# schema5.net
KiCad netlist of a schematic drawn in Altium Designer
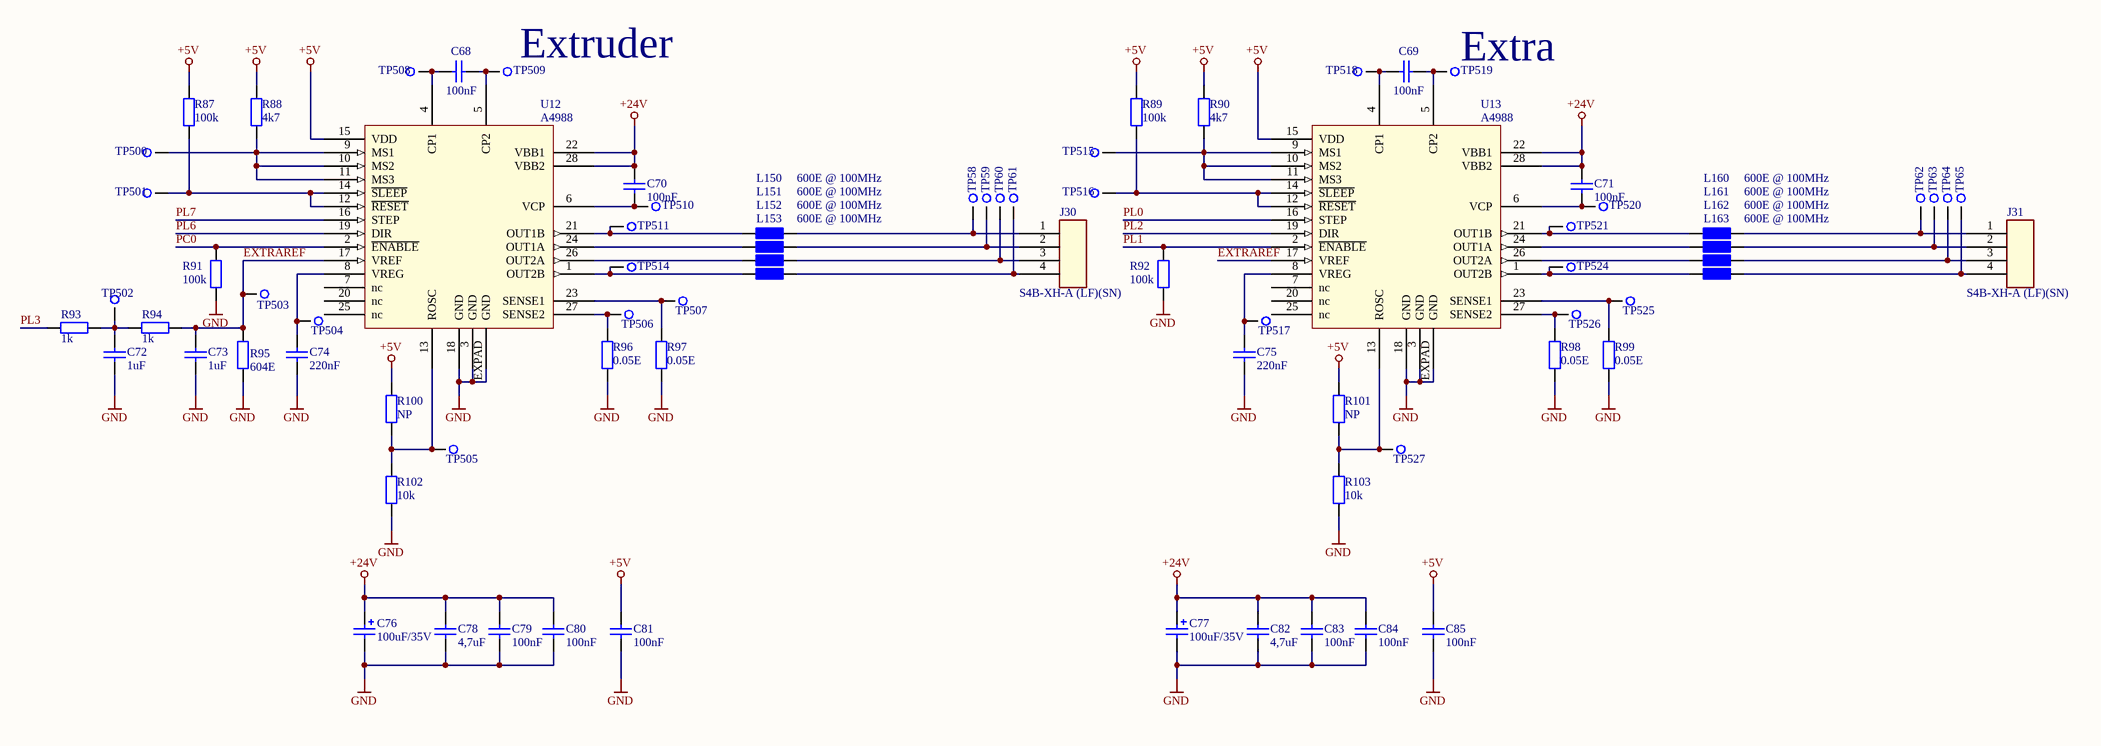
[diagram p0: schema5.SchDoc]

(export (version "E")
  (design (tool "Eeschema 10.0.6"))
  (components
    (comp (ref "C68")
      (value "100nF")
      (footprint "C0603")
      (description "RO X7R 100nF 10% 50V 0603")
      (libsource (lib "Database_Faber") (part "Capacitor"))
    )
    (comp (ref "C69")
      (value "100nF")
      (footprint "C0603")
      (description "RO X7R 100nF 10% 50V 0603")
      (libsource (lib "Database_Faber") (part "Capacitor"))
    )
    (comp (ref "C70")
      (value "100nF")
      (footprint "C0603")
      (description "RO X7R 100nF 10% 50V 0603")
      (libsource (lib "Database_Faber") (part "Capacitor"))
    )
    (comp (ref "C71")
      (value "100nF")
      (footprint "C0603")
      (description "RO X7R 100nF 10% 50V 0603")
      (libsource (lib "Database_Faber") (part "Capacitor"))
    )
    (comp (ref "C72")
      (value "1uF")
      (footprint "C0603")
      (description "RO X5R 1uF 10% 10V 0603")
      (libsource (lib "Database_Faber") (part "Capacitor"))
    )
    (comp (ref "C73")
      (value "1uF")
      (footprint "C0603")
      (description "RO X5R 1uF 10% 10V 0603")
      (libsource (lib "Database_Faber") (part "Capacitor"))
    )
    (comp (ref "C74")
      (value "220nF")
      (footprint "C0603")
      (description "RO X7R 220nF 10% 25V  0603")
      (libsource (lib "Database_Faber") (part "Capacitor"))
    )
    (comp (ref "C75")
      (value "220nF")
      (footprint "C0603")
      (description "RO X7R 220nF 10% 25V  0603")
      (libsource (lib "Database_Faber") (part "Capacitor"))
    )
    (comp (ref "C76")
      (value "100uF/35V")
      (footprint "ELCO Case D")
      (description "RO ELCO 100uF 20% 35V CASE-D EEEFP PAN")
      (libsource (lib "Database_Faber") (part "Capacitor Polarity"))
    )
    (comp (ref "C77")
      (value "100uF/35V")
      (footprint "ELCO Case D")
      (description "RO ELCO 100uF 20% 35V CASE-D EEEFP PAN")
      (libsource (lib "Database_Faber") (part "Capacitor Polarity"))
    )
    (comp (ref "C78")
      (value "4,7uF")
      (footprint "C1206")
      (description "RO X7R 4,7uF 10% 50V 1206")
      (libsource (lib "Database_Faber") (part "Capacitor"))
    )
    (comp (ref "C79")
      (value "100nF")
      (footprint "C0603")
      (description "RO X7R 100nF 10% 50V 0603")
      (libsource (lib "Database_Faber") (part "Capacitor"))
    )
    (comp (ref "C80")
      (value "100nF")
      (footprint "C0603")
      (description "RO X7R 100nF 10% 50V 0603")
      (libsource (lib "Database_Faber") (part "Capacitor"))
    )
    (comp (ref "C81")
      (value "100nF")
      (footprint "C0603")
      (description "RO X7R 100nF 10% 50V 0603")
      (libsource (lib "Database_Faber") (part "Capacitor"))
    )
    (comp (ref "C82")
      (value "4,7uF")
      (footprint "C1206")
      (description "RO X7R 4,7uF 10% 50V 1206")
      (libsource (lib "Database_Faber") (part "Capacitor"))
    )
    (comp (ref "C83")
      (value "100nF")
      (footprint "C0603")
      (description "RO X7R 100nF 10% 50V 0603")
      (libsource (lib "Database_Faber") (part "Capacitor"))
    )
    (comp (ref "C84")
      (value "100nF")
      (footprint "C0603")
      (description "RO X7R 100nF 10% 50V 0603")
      (libsource (lib "Database_Faber") (part "Capacitor"))
    )
    (comp (ref "C85")
      (value "100nF")
      (footprint "C0603")
      (description "RO X7R 100nF 10% 50V 0603")
      (libsource (lib "Database_Faber") (part "Capacitor"))
    )
    (comp (ref "J30")
      (value "S4B-XH-A (LF)(SN)")
      (footprint "S4B-XH-A (LF)(SN)")
      (description "RO CONN PR 4p HKS S4B-XH-A (LF)(SN) JST")
      (fields (field (name "MFG") "JST (JAPAN SOLDERLESS TERMINALS)"))
      (libsource (lib "Database_Faber") (part "HEADER 4"))
    )
    (comp (ref "J31")
      (value "S4B-XH-A (LF)(SN)")
      (footprint "S4B-XH-A (LF)(SN)")
      (description "RO CONN PR 4p HKS S4B-XH-A (LF)(SN) JST")
      (fields (field (name "MFG") "JST (JAPAN SOLDERLESS TERMINALS)"))
      (libsource (lib "Database_Faber") (part "HEADER 4"))
    )
    (comp (ref "L150")
      (value "600E @ 100MHz")
      (footprint "R1206")
      (description "FERRIET 742792118 1206 Wurth Elektronik")
      (fields (field (name "MFG") "Wurth Elektronics"))
      (libsource (lib "Ultimaker") (part "Ferriet Bead 600E"))
    )
    (comp (ref "L151")
      (value "600E @ 100MHz")
      (footprint "R1206")
      (description "FERRIET 742792118 1206 Wurth Elektronik")
      (fields (field (name "MFG") "Wurth Elektronics"))
      (libsource (lib "Ultimaker") (part "Ferriet Bead 600E"))
    )
    (comp (ref "L152")
      (value "600E @ 100MHz")
      (footprint "R1206")
      (description "FERRIET 742792118 1206 Wurth Elektronik")
      (fields (field (name "MFG") "Wurth Elektronics"))
      (libsource (lib "Ultimaker") (part "Ferriet Bead 600E"))
    )
    (comp (ref "L153")
      (value "600E @ 100MHz")
      (footprint "R1206")
      (description "FERRIET 742792118 1206 Wurth Elektronik")
      (fields (field (name "MFG") "Wurth Elektronics"))
      (libsource (lib "Ultimaker") (part "Ferriet Bead 600E"))
    )
    (comp (ref "L160")
      (value "600E @ 100MHz")
      (footprint "R1206")
      (description "FERRIET 742792118 1206 Wurth Elektronik")
      (fields (field (name "MFG") "Wurth Elektronics"))
      (libsource (lib "Ultimaker") (part "Ferriet Bead 600E"))
    )
    (comp (ref "L161")
      (value "600E @ 100MHz")
      (footprint "R1206")
      (description "FERRIET 742792118 1206 Wurth Elektronik")
      (fields (field (name "MFG") "Wurth Elektronics"))
      (libsource (lib "Ultimaker") (part "Ferriet Bead 600E"))
    )
    (comp (ref "L162")
      (value "600E @ 100MHz")
      (footprint "R1206")
      (description "FERRIET 742792118 1206 Wurth Elektronik")
      (fields (field (name "MFG") "Wurth Elektronics"))
      (libsource (lib "Ultimaker") (part "Ferriet Bead 600E"))
    )
    (comp (ref "L163")
      (value "600E @ 100MHz")
      (footprint "R1206")
      (description "FERRIET 742792118 1206 Wurth Elektronik")
      (fields (field (name "MFG") "Wurth Elektronics"))
      (libsource (lib "Ultimaker") (part "Ferriet Bead 600E"))
    )
    (comp (ref "R87")
      (value "100k")
      (footprint "R0603")
      (description "RO RES 100k0 1% 0,063W  0603")
      (libsource (lib "") (part "Resistor_1"))
    )
    (comp (ref "R88")
      (value "4k7")
      (footprint "R0603")
      (description "RO RES 4k70 1% 0,063W  0603")
      (libsource (lib "") (part "Resistor_1"))
    )
    (comp (ref "R89")
      (value "100k")
      (footprint "R0603")
      (description "RO RES 100k0 1% 0,063W  0603")
      (libsource (lib "") (part "Resistor_1"))
    )
    (comp (ref "R90")
      (value "4k7")
      (footprint "R0603")
      (description "RO RES 4k70 1% 0,063W  0603")
      (libsource (lib "") (part "Resistor_1"))
    )
    (comp (ref "R91")
      (value "100k")
      (footprint "R0603")
      (description "RO RES 100k0 1% 0,063W  0603")
      (libsource (lib "Database_Faber") (part "Resistor"))
    )
    (comp (ref "R92")
      (value "100k")
      (footprint "R0603")
      (description "RO RES 100k0 1% 0,063W  0603")
      (libsource (lib "Database_Faber") (part "Resistor"))
    )
    (comp (ref "R93")
      (value "1k")
      (footprint "R0603")
      (description "RO RES 1k0 1% 0,1W  0603")
      (libsource (lib "") (part "Resistor_2"))
    )
    (comp (ref "R94")
      (value "1k")
      (footprint "R0603")
      (description "RO RES 1k0 1% 0,1W  0603")
      (libsource (lib "") (part "Resistor_2"))
    )
    (comp (ref "R95")
      (value "604E")
      (footprint "R0603")
      (description "RO RES 604E 1% 0,063W 0603")
      (fields (field (name "MFG") "VISHAY DRALORIC"))
      (libsource (lib "") (part "Resistor_1"))
    )
    (comp (ref "R96")
      (value "0.05E")
      (footprint "R0805")
      (description "RO RES 0E05 1% 0,125W 0805")
      (fields (field (name "MFG") "BOURNS"))
      (libsource (lib "") (part "Resistor_1"))
    )
    (comp (ref "R97")
      (value "0.05E")
      (footprint "R0805")
      (description "RO RES 0E05 1% 0,125W 0805")
      (fields (field (name "MFG") "BOURNS"))
      (libsource (lib "") (part "Resistor_1"))
    )
    (comp (ref "R98")
      (value "0.05E")
      (footprint "R0805")
      (description "RO RES 0E05 1% 0,125W 0805")
      (fields (field (name "MFG") "BOURNS"))
      (libsource (lib "") (part "Resistor_1"))
    )
    (comp (ref "R99")
      (value "0.05E")
      (footprint "R0805")
      (description "RO RES 0E05 1% 0,125W 0805")
      (fields (field (name "MFG") "BOURNS"))
      (libsource (lib "") (part "Resistor_1"))
    )
    (comp (ref "R100") (value "NP") (footprint "R0603") (libsource (lib "") (part "Resistor_1")))
    (comp (ref "R101") (value "NP") (footprint "R0603") (libsource (lib "") (part "Resistor_1")))
    (comp (ref "R102")
      (value "10k")
      (footprint "R0603")
      (description "RO RES 10k0 1% 0,063W  0603")
      (libsource (lib "") (part "Resistor_1"))
    )
    (comp (ref "R103")
      (value "10k")
      (footprint "R0603")
      (description "RO RES 10k0 1% 0,063W  0603")
      (libsource (lib "") (part "Resistor_1"))
    )
    (comp (ref "TP58")
      (value "Testpoint")
      (footprint "Testpoint")
      (libsource (lib "Database_Faber") (part "Testpoint"))
    )
    (comp (ref "TP59")
      (value "Testpoint")
      (footprint "Testpoint")
      (libsource (lib "Database_Faber") (part "Testpoint"))
    )
    (comp (ref "TP60")
      (value "Testpoint")
      (footprint "Testpoint")
      (libsource (lib "Database_Faber") (part "Testpoint"))
    )
    (comp (ref "TP61")
      (value "Testpoint")
      (footprint "Testpoint")
      (libsource (lib "Database_Faber") (part "Testpoint"))
    )
    (comp (ref "TP62")
      (value "Testpoint")
      (footprint "Testpoint")
      (libsource (lib "Database_Faber") (part "Testpoint"))
    )
    (comp (ref "TP63")
      (value "Testpoint")
      (footprint "Testpoint")
      (libsource (lib "Database_Faber") (part "Testpoint"))
    )
    (comp (ref "TP64")
      (value "Testpoint")
      (footprint "Testpoint")
      (libsource (lib "Database_Faber") (part "Testpoint"))
    )
    (comp (ref "TP65")
      (value "Testpoint")
      (footprint "Testpoint")
      (libsource (lib "Database_Faber") (part "Testpoint"))
    )
    (comp (ref "TP500")
      (value "Testpoint 1mm")
      (footprint "Testpoint 1mm")
      (libsource (lib "Ultimaker") (part "Testpoint 1mm"))
    )
    (comp (ref "TP501")
      (value "Testpoint 1mm")
      (footprint "Testpoint 1mm")
      (libsource (lib "Ultimaker") (part "Testpoint 1mm"))
    )
    (comp (ref "TP502")
      (value "Testpoint 1mm")
      (footprint "Testpoint 1mm")
      (libsource (lib "Ultimaker") (part "Testpoint 1mm"))
    )
    (comp (ref "TP503")
      (value "Testpoint 1mm")
      (footprint "Testpoint 1mm")
      (libsource (lib "Ultimaker") (part "Testpoint 1mm"))
    )
    (comp (ref "TP504")
      (value "Testpoint 1mm")
      (footprint "Testpoint 1mm")
      (libsource (lib "Ultimaker") (part "Testpoint 1mm"))
    )
    (comp (ref "TP505")
      (value "Testpoint 1mm")
      (footprint "Testpoint 1mm")
      (libsource (lib "Ultimaker") (part "Testpoint 1mm"))
    )
    (comp (ref "TP506")
      (value "Testpoint 1mm")
      (footprint "Testpoint 1mm")
      (libsource (lib "Ultimaker") (part "Testpoint 1mm"))
    )
    (comp (ref "TP507")
      (value "Testpoint 1mm")
      (footprint "Testpoint 1mm")
      (libsource (lib "Ultimaker") (part "Testpoint 1mm"))
    )
    (comp (ref "TP508")
      (value "Testpoint 1mm")
      (footprint "Testpoint 1mm")
      (libsource (lib "Ultimaker") (part "Testpoint 1mm"))
    )
    (comp (ref "TP509")
      (value "Testpoint 1mm")
      (footprint "Testpoint 1mm")
      (libsource (lib "Ultimaker") (part "Testpoint 1mm"))
    )
    (comp (ref "TP510")
      (value "Testpoint 1mm")
      (footprint "Testpoint 1mm")
      (libsource (lib "Ultimaker") (part "Testpoint 1mm"))
    )
    (comp (ref "TP511")
      (value "Testpoint 1mm")
      (footprint "Testpoint 1mm")
      (libsource (lib "Ultimaker") (part "Testpoint 1mm"))
    )
    (comp (ref "TP514")
      (value "Testpoint 1mm")
      (footprint "Testpoint 1mm")
      (libsource (lib "Ultimaker") (part "Testpoint 1mm"))
    )
    (comp (ref "TP515")
      (value "Testpoint 1mm")
      (footprint "Testpoint 1mm")
      (libsource (lib "Ultimaker") (part "Testpoint 1mm"))
    )
    (comp (ref "TP516")
      (value "Testpoint 1mm")
      (footprint "Testpoint 1mm")
      (libsource (lib "Ultimaker") (part "Testpoint 1mm"))
    )
    (comp (ref "TP517")
      (value "Testpoint 1mm")
      (footprint "Testpoint 1mm")
      (libsource (lib "Ultimaker") (part "Testpoint 1mm"))
    )
    (comp (ref "TP518")
      (value "Testpoint 1mm")
      (footprint "Testpoint 1mm")
      (libsource (lib "Ultimaker") (part "Testpoint 1mm"))
    )
    (comp (ref "TP519")
      (value "Testpoint 1mm")
      (footprint "Testpoint 1mm")
      (libsource (lib "Ultimaker") (part "Testpoint 1mm"))
    )
    (comp (ref "TP520")
      (value "Testpoint 1mm")
      (footprint "Testpoint 1mm")
      (libsource (lib "Ultimaker") (part "Testpoint 1mm"))
    )
    (comp (ref "TP521")
      (value "Testpoint 1mm")
      (footprint "Testpoint 1mm")
      (libsource (lib "Ultimaker") (part "Testpoint 1mm"))
    )
    (comp (ref "TP524")
      (value "Testpoint 1mm")
      (footprint "Testpoint 1mm")
      (libsource (lib "Ultimaker") (part "Testpoint 1mm"))
    )
    (comp (ref "TP525")
      (value "Testpoint 1mm")
      (footprint "Testpoint 1mm")
      (libsource (lib "Ultimaker") (part "Testpoint 1mm"))
    )
    (comp (ref "TP526")
      (value "Testpoint 1mm")
      (footprint "Testpoint 1mm")
      (libsource (lib "Ultimaker") (part "Testpoint 1mm"))
    )
    (comp (ref "TP527")
      (value "Testpoint 1mm")
      (footprint "Testpoint 1mm")
      (libsource (lib "Ultimaker") (part "Testpoint 1mm"))
    )
    (comp (ref "U12")
      (value "A4988")
      (footprint "QFN50P500X500X100-28-EX")
      (description "RO IC A4988 QFN-28 ALLEGRO")
      (fields (field (name "MFG") "Allegro"))
      (libsource (lib "Database_Faber") (part "A4988"))
    )
    (comp (ref "U13")
      (value "A4988")
      (footprint "QFN50P500X500X100-28-EX")
      (description "RO IC A4988 QFN-28 ALLEGRO")
      (fields (field (name "MFG") "Allegro"))
      (libsource (lib "Database_Faber") (part "A4988"))
    )
  )
  (nets
    (net (code "1") (name "+5V") (class "Default")
      (node (ref "C81") (pin "2") (pinfunction "2_2") (pintype "passive"))
      (node (ref "C85") (pin "2") (pinfunction "2_2") (pintype "passive"))
      (node (ref "R100") (pin "2") (pinfunction "2_2") (pintype "passive"))
      (node (ref "R101") (pin "2") (pinfunction "2_2") (pintype "passive"))
      (node (ref "R87") (pin "2") (pinfunction "2_2") (pintype "passive"))
      (node (ref "R88") (pin "2") (pinfunction "2_2") (pintype "passive"))
      (node (ref "R89") (pin "2") (pinfunction "2_2") (pintype "passive"))
      (node (ref "R90") (pin "2") (pinfunction "2_2") (pintype "passive"))
      (node (ref "U12") (pin "15") (pinfunction "VDD_15") (pintype "power_in"))
      (node (ref "U13") (pin "15") (pinfunction "VDD_15") (pintype "power_in"))
    )
    (net (code "2") (name "+24V") (class "Default")
      (node (ref "C70") (pin "2") (pinfunction "2_2") (pintype "passive"))
      (node (ref "C71") (pin "2") (pinfunction "2_2") (pintype "passive"))
      (node (ref "C76") (pin "1") (pinfunction "1_1") (pintype "passive"))
      (node (ref "C77") (pin "1") (pinfunction "1_1") (pintype "passive"))
      (node (ref "C78") (pin "2") (pinfunction "2_2") (pintype "passive"))
      (node (ref "C79") (pin "2") (pinfunction "2_2") (pintype "passive"))
      (node (ref "C80") (pin "2") (pinfunction "2_2") (pintype "passive"))
      (node (ref "C82") (pin "2") (pinfunction "2_2") (pintype "passive"))
      (node (ref "C83") (pin "2") (pinfunction "2_2") (pintype "passive"))
      (node (ref "C84") (pin "2") (pinfunction "2_2") (pintype "passive"))
      (node (ref "U12") (pin "22") (pinfunction "VBB1_22") (pintype "power_in"))
      (node (ref "U12") (pin "28") (pinfunction "VBB2_28") (pintype "power_in"))
      (node (ref "U13") (pin "22") (pinfunction "VBB1_22") (pintype "power_in"))
      (node (ref "U13") (pin "28") (pinfunction "VBB2_28") (pintype "power_in"))
    )
    (net (code "3") (name "/EXTRAREF") (class "Default")
      (node (ref "C73") (pin "2") (pinfunction "2_2") (pintype "passive"))
      (node (ref "R94") (pin "2") (pinfunction "2_2") (pintype "passive"))
      (node (ref "R95") (pin "2") (pinfunction "2_2") (pintype "passive"))
      (node (ref "TP503") (pin "1") (pinfunction "1_1") (pintype "passive"))
      (node (ref "U12") (pin "17") (pinfunction "VREF_17") (pintype "input"))
      (node (ref "U13") (pin "17") (pinfunction "VREF_17") (pintype "input"))
    )
    (net (code "4") (name "/PC0") (class "Default")
      (node (ref "R91") (pin "1") (pinfunction "1_1") (pintype "passive"))
      (node (ref "U12") (pin "2") (pinfunction "~{ENABLE}_2") (pintype "input"))
    )
    (net (code "5") (name "/PL0") (class "Default")
      (node (ref "U13") (pin "16") (pinfunction "STEP_16") (pintype "input"))
    )
    (net (code "6") (name "/PL1") (class "Default")
      (node (ref "R92") (pin "1") (pinfunction "1_1") (pintype "passive"))
      (node (ref "U13") (pin "2") (pinfunction "~{ENABLE}_2") (pintype "input"))
    )
    (net (code "7") (name "/PL2") (class "Default")
      (node (ref "U13") (pin "19") (pinfunction "DIR_19") (pintype "input"))
    )
    (net (code "8") (name "/PL3") (class "Default")
      (node (ref "R93") (pin "1") (pinfunction "1_1") (pintype "passive"))
    )
    (net (code "9") (name "/PL6") (class "Default")
      (node (ref "U12") (pin "19") (pinfunction "DIR_19") (pintype "input"))
    )
    (net (code "10") (name "/PL7") (class "Default")
      (node (ref "U12") (pin "16") (pinfunction "STEP_16") (pintype "input"))
    )
    (net (code "11") (name "GND") (class "Default")
      (node (ref "C72") (pin "1") (pinfunction "1_1") (pintype "passive"))
      (node (ref "C73") (pin "1") (pinfunction "1_1") (pintype "passive"))
      (node (ref "C74") (pin "1") (pinfunction "1_1") (pintype "passive"))
      (node (ref "C75") (pin "1") (pinfunction "1_1") (pintype "passive"))
      (node (ref "C76") (pin "2") (pinfunction "2_2") (pintype "passive"))
      (node (ref "C77") (pin "2") (pinfunction "2_2") (pintype "passive"))
      (node (ref "C78") (pin "1") (pinfunction "1_1") (pintype "passive"))
      (node (ref "C79") (pin "1") (pinfunction "1_1") (pintype "passive"))
      (node (ref "C80") (pin "1") (pinfunction "1_1") (pintype "passive"))
      (node (ref "C81") (pin "1") (pinfunction "1_1") (pintype "passive"))
      (node (ref "C82") (pin "1") (pinfunction "1_1") (pintype "passive"))
      (node (ref "C83") (pin "1") (pinfunction "1_1") (pintype "passive"))
      (node (ref "C84") (pin "1") (pinfunction "1_1") (pintype "passive"))
      (node (ref "C85") (pin "1") (pinfunction "1_1") (pintype "passive"))
      (node (ref "R102") (pin "1") (pinfunction "1_1") (pintype "passive"))
      (node (ref "R103") (pin "1") (pinfunction "1_1") (pintype "passive"))
      (node (ref "R91") (pin "2") (pinfunction "2_2") (pintype "passive"))
      (node (ref "R92") (pin "2") (pinfunction "2_2") (pintype "passive"))
      (node (ref "R95") (pin "1") (pinfunction "1_1") (pintype "passive"))
      (node (ref "R96") (pin "1") (pinfunction "1_1") (pintype "passive"))
      (node (ref "R97") (pin "1") (pinfunction "1_1") (pintype "passive"))
      (node (ref "R98") (pin "1") (pinfunction "1_1") (pintype "passive"))
      (node (ref "R99") (pin "1") (pinfunction "1_1") (pintype "passive"))
      (node (ref "U12") (pin "18") (pinfunction "GND_18") (pintype "passive"))
      (node (ref "U12") (pin "3") (pinfunction "GND_3") (pintype "power_in"))
      (node (ref "U12") (pin "EXPAD") (pinfunction "GND_EXPAD") (pintype "power_in"))
      (node (ref "U13") (pin "18") (pinfunction "GND_18") (pintype "passive"))
      (node (ref "U13") (pin "3") (pinfunction "GND_3") (pintype "power_in"))
      (node (ref "U13") (pin "EXPAD") (pinfunction "GND_EXPAD") (pintype "power_in"))
    )
    (net (code "12") (name "Net-(C72-Pad2)") (class "Default")
      (node (ref "C72") (pin "2") (pinfunction "2_2") (pintype "passive"))
      (node (ref "R93") (pin "2") (pinfunction "2_2") (pintype "passive"))
      (node (ref "R94") (pin "1") (pinfunction "1_1") (pintype "passive"))
      (node (ref "TP502") (pin "1") (pinfunction "1_1") (pintype "passive"))
    )
    (net (code "13") (name "Net-(J30-Pad1)") (class "Default")
      (node (ref "J30") (pin "1") (pinfunction "1_1") (pintype "passive"))
      (node (ref "L150") (pin "2") (pinfunction "2_2") (pintype "passive"))
      (node (ref "TP58") (pin "1") (pinfunction "1_1") (pintype "passive"))
    )
    (net (code "14") (name "Net-(J30-Pad2)") (class "Default")
      (node (ref "J30") (pin "2") (pinfunction "2_2") (pintype "passive"))
      (node (ref "L151") (pin "2") (pinfunction "2_2") (pintype "passive"))
      (node (ref "TP59") (pin "1") (pinfunction "1_1") (pintype "passive"))
    )
    (net (code "15") (name "Net-(J30-Pad3)") (class "Default")
      (node (ref "J30") (pin "3") (pinfunction "3_3") (pintype "passive"))
      (node (ref "L152") (pin "2") (pinfunction "2_2") (pintype "passive"))
      (node (ref "TP60") (pin "1") (pinfunction "1_1") (pintype "passive"))
    )
    (net (code "16") (name "Net-(J30-Pad4)") (class "Default")
      (node (ref "J30") (pin "4") (pinfunction "4_4") (pintype "passive"))
      (node (ref "L153") (pin "2") (pinfunction "2_2") (pintype "passive"))
      (node (ref "TP61") (pin "1") (pinfunction "1_1") (pintype "passive"))
    )
    (net (code "17") (name "Net-(J31-Pad1)") (class "Default")
      (node (ref "J31") (pin "1") (pinfunction "1_1") (pintype "passive"))
      (node (ref "L160") (pin "2") (pinfunction "2_2") (pintype "passive"))
      (node (ref "TP62") (pin "1") (pinfunction "1_1") (pintype "passive"))
    )
    (net (code "18") (name "Net-(J31-Pad2)") (class "Default")
      (node (ref "J31") (pin "2") (pinfunction "2_2") (pintype "passive"))
      (node (ref "L161") (pin "2") (pinfunction "2_2") (pintype "passive"))
      (node (ref "TP63") (pin "1") (pinfunction "1_1") (pintype "passive"))
    )
    (net (code "19") (name "Net-(J31-Pad3)") (class "Default")
      (node (ref "J31") (pin "3") (pinfunction "3_3") (pintype "passive"))
      (node (ref "L162") (pin "2") (pinfunction "2_2") (pintype "passive"))
      (node (ref "TP64") (pin "1") (pinfunction "1_1") (pintype "passive"))
    )
    (net (code "20") (name "Net-(J31-Pad4)") (class "Default")
      (node (ref "J31") (pin "4") (pinfunction "4_4") (pintype "passive"))
      (node (ref "L163") (pin "2") (pinfunction "2_2") (pintype "passive"))
      (node (ref "TP65") (pin "1") (pinfunction "1_1") (pintype "passive"))
    )
    (net (code "21") (name "Net-(U12-CP1)") (class "Default")
      (node (ref "C68") (pin "1") (pinfunction "1_1") (pintype "passive"))
      (node (ref "TP508") (pin "1") (pinfunction "1_1") (pintype "passive"))
      (node (ref "U12") (pin "4") (pinfunction "CP1_4") (pintype "passive"))
    )
    (net (code "22") (name "Net-(U12-CP2)") (class "Default")
      (node (ref "C68") (pin "2") (pinfunction "2_2") (pintype "passive"))
      (node (ref "TP509") (pin "1") (pinfunction "1_1") (pintype "passive"))
      (node (ref "U12") (pin "5") (pinfunction "CP2_5") (pintype "passive"))
    )
    (net (code "23") (name "Net-(U12-MS1)") (class "Default")
      (node (ref "R88") (pin "1") (pinfunction "1_1") (pintype "passive"))
      (node (ref "TP500") (pin "1") (pinfunction "1_1") (pintype "passive"))
      (node (ref "U12") (pin "10") (pinfunction "MS2_10") (pintype "input"))
      (node (ref "U12") (pin "11") (pinfunction "MS3_11") (pintype "input"))
      (node (ref "U12") (pin "9") (pinfunction "MS1_9") (pintype "input"))
    )
    (net (code "24") (name "Net-(U12-OUT1A)") (class "Default")
      (node (ref "L151") (pin "1") (pinfunction "1_1") (pintype "passive"))
      (node (ref "U12") (pin "24") (pinfunction "OUT1A_24") (pintype "output"))
    )
    (net (code "25") (name "Net-(U12-OUT1B)") (class "Default")
      (node (ref "L150") (pin "1") (pinfunction "1_1") (pintype "passive"))
      (node (ref "TP511") (pin "1") (pinfunction "1_1") (pintype "passive"))
      (node (ref "U12") (pin "21") (pinfunction "OUT1B_21") (pintype "output"))
    )
    (net (code "26") (name "Net-(U12-OUT2A)") (class "Default")
      (node (ref "L152") (pin "1") (pinfunction "1_1") (pintype "passive"))
      (node (ref "U12") (pin "26") (pinfunction "OUT2A_26") (pintype "output"))
    )
    (net (code "27") (name "Net-(U12-OUT2B)") (class "Default")
      (node (ref "L153") (pin "1") (pinfunction "1_1") (pintype "passive"))
      (node (ref "TP514") (pin "1") (pinfunction "1_1") (pintype "passive"))
      (node (ref "U12") (pin "1") (pinfunction "OUT2B_1") (pintype "output"))
    )
    (net (code "28") (name "Net-(U12-ROSC)") (class "Default")
      (node (ref "R100") (pin "1") (pinfunction "1_1") (pintype "passive"))
      (node (ref "R102") (pin "2") (pinfunction "2_2") (pintype "passive"))
      (node (ref "TP505") (pin "1") (pinfunction "1_1") (pintype "passive"))
      (node (ref "U12") (pin "13") (pinfunction "ROSC_13") (pintype "passive"))
    )
    (net (code "29") (name "Net-(U12-SENSE1)") (class "Default")
      (node (ref "R97") (pin "2") (pinfunction "2_2") (pintype "passive"))
      (node (ref "TP507") (pin "1") (pinfunction "1_1") (pintype "passive"))
      (node (ref "U12") (pin "23") (pinfunction "SENSE1_23") (pintype "passive"))
    )
    (net (code "30") (name "Net-(U12-SENSE2)") (class "Default")
      (node (ref "R96") (pin "2") (pinfunction "2_2") (pintype "passive"))
      (node (ref "TP506") (pin "1") (pinfunction "1_1") (pintype "passive"))
      (node (ref "U12") (pin "27") (pinfunction "SENSE2_27") (pintype "passive"))
    )
    (net (code "31") (name "Net-(U12-VCP)") (class "Default")
      (node (ref "C70") (pin "1") (pinfunction "1_1") (pintype "passive"))
      (node (ref "TP510") (pin "1") (pinfunction "1_1") (pintype "passive"))
      (node (ref "U12") (pin "6") (pinfunction "VCP_6") (pintype "passive"))
    )
    (net (code "32") (name "Net-(U12-VREG)") (class "Default")
      (node (ref "C74") (pin "2") (pinfunction "2_2") (pintype "passive"))
      (node (ref "TP504") (pin "1") (pinfunction "1_1") (pintype "passive"))
      (node (ref "U12") (pin "8") (pinfunction "VREG_8") (pintype "power_in"))
    )
    (net (code "33") (name "Net-(U12-~{RESET})") (class "Default")
      (node (ref "R87") (pin "1") (pinfunction "1_1") (pintype "passive"))
      (node (ref "TP501") (pin "1") (pinfunction "1_1") (pintype "passive"))
      (node (ref "U12") (pin "12") (pinfunction "~{RESET}_12") (pintype "input"))
      (node (ref "U12") (pin "14") (pinfunction "~{SLEEP}_14") (pintype "input"))
    )
    (net (code "34") (name "Net-(U13-CP1)") (class "Default")
      (node (ref "C69") (pin "1") (pinfunction "1_1") (pintype "passive"))
      (node (ref "TP518") (pin "1") (pinfunction "1_1") (pintype "passive"))
      (node (ref "U13") (pin "4") (pinfunction "CP1_4") (pintype "passive"))
    )
    (net (code "35") (name "Net-(U13-CP2)") (class "Default")
      (node (ref "C69") (pin "2") (pinfunction "2_2") (pintype "passive"))
      (node (ref "TP519") (pin "1") (pinfunction "1_1") (pintype "passive"))
      (node (ref "U13") (pin "5") (pinfunction "CP2_5") (pintype "passive"))
    )
    (net (code "36") (name "Net-(U13-MS1)") (class "Default")
      (node (ref "R90") (pin "1") (pinfunction "1_1") (pintype "passive"))
      (node (ref "TP515") (pin "1") (pinfunction "1_1") (pintype "passive"))
      (node (ref "U13") (pin "10") (pinfunction "MS2_10") (pintype "input"))
      (node (ref "U13") (pin "11") (pinfunction "MS3_11") (pintype "input"))
      (node (ref "U13") (pin "9") (pinfunction "MS1_9") (pintype "input"))
    )
    (net (code "37") (name "Net-(U13-OUT1A)") (class "Default")
      (node (ref "L161") (pin "1") (pinfunction "1_1") (pintype "passive"))
      (node (ref "U13") (pin "24") (pinfunction "OUT1A_24") (pintype "output"))
    )
    (net (code "38") (name "Net-(U13-OUT1B)") (class "Default")
      (node (ref "L160") (pin "1") (pinfunction "1_1") (pintype "passive"))
      (node (ref "TP521") (pin "1") (pinfunction "1_1") (pintype "passive"))
      (node (ref "U13") (pin "21") (pinfunction "OUT1B_21") (pintype "output"))
    )
    (net (code "39") (name "Net-(U13-OUT2A)") (class "Default")
      (node (ref "L162") (pin "1") (pinfunction "1_1") (pintype "passive"))
      (node (ref "U13") (pin "26") (pinfunction "OUT2A_26") (pintype "output"))
    )
    (net (code "40") (name "Net-(U13-OUT2B)") (class "Default")
      (node (ref "L163") (pin "1") (pinfunction "1_1") (pintype "passive"))
      (node (ref "TP524") (pin "1") (pinfunction "1_1") (pintype "passive"))
      (node (ref "U13") (pin "1") (pinfunction "OUT2B_1") (pintype "output"))
    )
    (net (code "41") (name "Net-(U13-ROSC)") (class "Default")
      (node (ref "R101") (pin "1") (pinfunction "1_1") (pintype "passive"))
      (node (ref "R103") (pin "2") (pinfunction "2_2") (pintype "passive"))
      (node (ref "TP527") (pin "1") (pinfunction "1_1") (pintype "passive"))
      (node (ref "U13") (pin "13") (pinfunction "ROSC_13") (pintype "passive"))
    )
    (net (code "42") (name "Net-(U13-SENSE1)") (class "Default")
      (node (ref "R99") (pin "2") (pinfunction "2_2") (pintype "passive"))
      (node (ref "TP525") (pin "1") (pinfunction "1_1") (pintype "passive"))
      (node (ref "U13") (pin "23") (pinfunction "SENSE1_23") (pintype "passive"))
    )
    (net (code "43") (name "Net-(U13-SENSE2)") (class "Default")
      (node (ref "R98") (pin "2") (pinfunction "2_2") (pintype "passive"))
      (node (ref "TP526") (pin "1") (pinfunction "1_1") (pintype "passive"))
      (node (ref "U13") (pin "27") (pinfunction "SENSE2_27") (pintype "passive"))
    )
    (net (code "44") (name "Net-(U13-VCP)") (class "Default")
      (node (ref "C71") (pin "1") (pinfunction "1_1") (pintype "passive"))
      (node (ref "TP520") (pin "1") (pinfunction "1_1") (pintype "passive"))
      (node (ref "U13") (pin "6") (pinfunction "VCP_6") (pintype "passive"))
    )
    (net (code "45") (name "Net-(U13-VREG)") (class "Default")
      (node (ref "C75") (pin "2") (pinfunction "2_2") (pintype "passive"))
      (node (ref "TP517") (pin "1") (pinfunction "1_1") (pintype "passive"))
      (node (ref "U13") (pin "8") (pinfunction "VREG_8") (pintype "power_in"))
    )
    (net (code "46") (name "Net-(U13-~{RESET})") (class "Default")
      (node (ref "R89") (pin "1") (pinfunction "1_1") (pintype "passive"))
      (node (ref "TP516") (pin "1") (pinfunction "1_1") (pintype "passive"))
      (node (ref "U13") (pin "12") (pinfunction "~{RESET}_12") (pintype "input"))
      (node (ref "U13") (pin "14") (pinfunction "~{SLEEP}_14") (pintype "input"))
    )
    (net (code "47") (name "unconnected-(U12-nc-Pad7)") (class "Default")
      (node (ref "U12") (pin "7") (pinfunction "nc_7") (pintype "passive"))
    )
    (net (code "48") (name "unconnected-(U12-nc-Pad20)") (class "Default")
      (node (ref "U12") (pin "20") (pinfunction "nc_20") (pintype "passive"))
    )
    (net (code "49") (name "unconnected-(U12-nc-Pad25)") (class "Default")
      (node (ref "U12") (pin "25") (pinfunction "nc_25") (pintype "passive"))
    )
    (net (code "50") (name "unconnected-(U13-nc-Pad7)") (class "Default")
      (node (ref "U13") (pin "7") (pinfunction "nc_7") (pintype "passive"))
    )
    (net (code "51") (name "unconnected-(U13-nc-Pad20)") (class "Default")
      (node (ref "U13") (pin "20") (pinfunction "nc_20") (pintype "passive"))
    )
    (net (code "52") (name "unconnected-(U13-nc-Pad25)") (class "Default")
      (node (ref "U13") (pin "25") (pinfunction "nc_25") (pintype "passive"))
    )
  )
)
